# signal_processor_of_UAV.net
KiCad netlist of a schematic drawn in Altium Designer
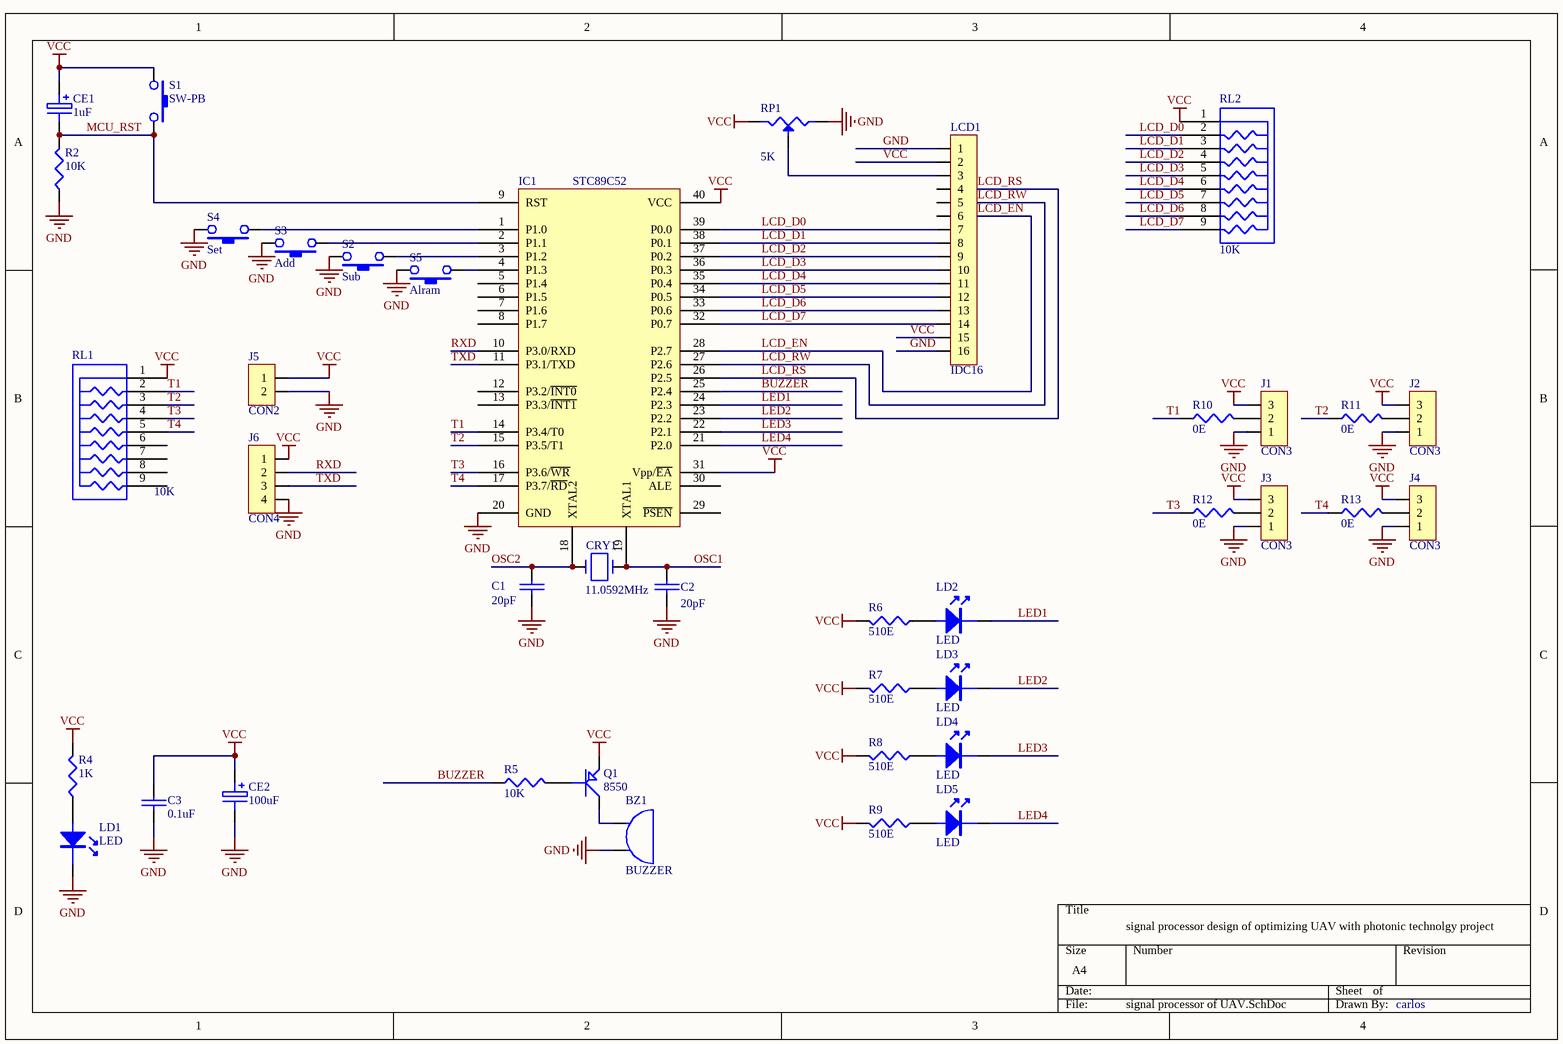
[diagram p0: signal processor of UAV.SchDoc]

(export (version "E")
  (design (tool "Eeschema 10.0.6"))
  (components
    (comp (ref "BZ1") (value "BUZZER") (footprint "BUZZER1") (libsource (lib "Sch1") (part "BUZZER")))
    (comp (ref "C1")
      (value "20pF")
      (footprint "RAD0.1")
      (description "Capacitor")
      (libsource (lib "*") (part "CAP"))
    )
    (comp (ref "C2")
      (value "20pF")
      (footprint "RAD0.1")
      (description "Capacitor")
      (libsource (lib "*") (part "CAP"))
    )
    (comp (ref "C3") (value "0.1uF") (footprint "RAD0.1") (libsource (lib "Sch1") (part "CAP")))
    (comp (ref "CE1") (value "1uF") (footprint "RB.1/.1L") (libsource (lib "Sch1") (part "ELECTRO1")))
    (comp (ref "CE2") (value "100uF") (footprint "RB.1/.2") (libsource (lib "Sch1") (part "ELECTRO1")))
    (comp (ref "CRY1") (value "11.0592MHz") (footprint "XTAL1") (libsource (lib "*") (part "CRYSTAL")))
    (comp (ref "IC1") (value "STC89C52") (footprint "DIP40") (libsource (lib "Sch") (part "AT89C51")))
    (comp (ref "J1") (value "CON3") (footprint "HJ3P2.54") (libsource (lib "Sch1") (part "CON3")))
    (comp (ref "J2") (value "CON3") (footprint "HJ3P2.54") (libsource (lib "Sch1") (part "CON3")))
    (comp (ref "J3") (value "CON3") (footprint "HJ3P2.54") (libsource (lib "Sch1") (part "CON3")))
    (comp (ref "J4") (value "CON3") (footprint "HJ3P2.54") (libsource (lib "Sch1") (part "CON3")))
    (comp (ref "J5") (value "CON2") (footprint "HJ2P2.54") (libsource (lib "Sch1") (part "CON2")))
    (comp (ref "J6") (value "CON4") (footprint "HJ4P2.54") (libsource (lib "Sch1") (part "CON4")))
    (comp (ref "LCD1") (value "IDC16") (footprint "LCD1602A") (libsource (lib "Sch1") (part "CON16")))
    (comp (ref "LD1") (value "LED") (footprint "LEDF3") (libsource (lib "Sch1") (part "LED")))
    (comp (ref "LD2") (value "LED") (footprint "LEDF3") (libsource (lib "Sch1") (part "LED")))
    (comp (ref "LD3") (value "LED") (footprint "LEDF3") (libsource (lib "Sch1") (part "LED")))
    (comp (ref "LD4") (value "LED") (footprint "LEDF3") (libsource (lib "Sch1") (part "LED")))
    (comp (ref "LD5") (value "LED") (footprint "LEDF3") (libsource (lib "Sch1") (part "LED")))
    (comp (ref "Q1") (value "8550") (footprint "TR-EBC") (libsource (lib "Sch1") (part "PNP1")))
    (comp (ref "R2") (value "10K") (footprint "AXIAL0.3") (libsource (lib "Sch1") (part "RES1")))
    (comp (ref "R4") (value "1K") (footprint "AXIAL0.3") (libsource (lib "Sch1") (part "RES1")))
    (comp (ref "R5") (value "10K") (footprint "AXIAL0.3") (libsource (lib "Sch1") (part "RES1")))
    (comp (ref "R6") (value "510E") (footprint "AXIAL0.3") (libsource (lib "Sch1") (part "RES1")))
    (comp (ref "R7") (value "510E") (footprint "AXIAL0.3") (libsource (lib "Sch1") (part "RES1")))
    (comp (ref "R8") (value "510E") (footprint "AXIAL0.3") (libsource (lib "Sch1") (part "RES1")))
    (comp (ref "R9") (value "510E") (footprint "AXIAL0.3") (libsource (lib "Sch1") (part "RES1")))
    (comp (ref "R10") (value "0E") (footprint "AXIAL0.3") (libsource (lib "Sch1") (part "RES1")))
    (comp (ref "R11") (value "0E") (footprint "AXIAL0.3") (libsource (lib "Sch1") (part "RES1")))
    (comp (ref "R12") (value "0E") (footprint "AXIAL0.3") (libsource (lib "Sch1") (part "RES1")))
    (comp (ref "R13") (value "0E") (footprint "AXIAL0.3") (libsource (lib "Sch1") (part "RES1")))
    (comp (ref "RL1") (value "10K") (footprint "RES9P") (libsource (lib "Sch1") (part "RESL1")))
    (comp (ref "RL2") (value "10K") (footprint "RES9P") (libsource (lib "Sch1") (part "RESL1")))
    (comp (ref "RP1") (value "5K") (footprint "WR1") (libsource (lib "Sch1") (part "POT1")))
    (comp (ref "S1") (value "SW-PB") (footprint "SW-PB4DS") (libsource (lib "Sch1") (part "SW-PB")))
    (comp (ref "S2") (value "Sub") (footprint "SW-PB4DS") (libsource (lib "Sch1") (part "SW-PB")))
    (comp (ref "S3") (value "Add") (footprint "SW-PB4DS") (libsource (lib "Sch1") (part "SW-PB")))
    (comp (ref "S4") (value "Set") (footprint "SW-PB4DS") (libsource (lib "Sch1") (part "SW-PB")))
    (comp (ref "S5") (value "Alram") (footprint "SW-PB4DS") (libsource (lib "Sch1") (part "SW-PB")))
  )
  (nets
    (net (code "1") (name "/BUZZER") (class "Default")
      (node (ref "IC1") (pin "25") (pinfunction "P2.4_25") (pintype "passive"))
      (node (ref "R5") (pin "1") (pintype "passive"))
    )
    (net (code "2") (name "/LCD_D0") (class "Default")
      (node (ref "IC1") (pin "39") (pinfunction "P0.0_39") (pintype "passive"))
      (node (ref "LCD1") (pin "7") (pinfunction "7_7") (pintype "passive"))
      (node (ref "RL2") (pin "2") (pinfunction "2_2") (pintype "passive"))
    )
    (net (code "3") (name "/LCD_D1") (class "Default")
      (node (ref "IC1") (pin "38") (pinfunction "P0.1_38") (pintype "passive"))
      (node (ref "LCD1") (pin "8") (pinfunction "8_8") (pintype "passive"))
      (node (ref "RL2") (pin "3") (pinfunction "3_3") (pintype "passive"))
    )
    (net (code "4") (name "/LCD_D2") (class "Default")
      (node (ref "IC1") (pin "37") (pinfunction "P0.2_37") (pintype "passive"))
      (node (ref "LCD1") (pin "9") (pinfunction "9_9") (pintype "passive"))
      (node (ref "RL2") (pin "4") (pinfunction "4_4") (pintype "passive"))
    )
    (net (code "5") (name "/LCD_D3") (class "Default")
      (node (ref "IC1") (pin "36") (pinfunction "P0.3_36") (pintype "passive"))
      (node (ref "LCD1") (pin "10") (pinfunction "10_10") (pintype "passive"))
      (node (ref "RL2") (pin "5") (pinfunction "5_5") (pintype "passive"))
    )
    (net (code "6") (name "/LCD_D4") (class "Default")
      (node (ref "IC1") (pin "35") (pinfunction "P0.4_35") (pintype "passive"))
      (node (ref "LCD1") (pin "11") (pinfunction "11_11") (pintype "passive"))
      (node (ref "RL2") (pin "6") (pinfunction "6_6") (pintype "passive"))
    )
    (net (code "7") (name "/LCD_D5") (class "Default")
      (node (ref "IC1") (pin "34") (pinfunction "P0.5_34") (pintype "passive"))
      (node (ref "LCD1") (pin "12") (pinfunction "12_12") (pintype "passive"))
      (node (ref "RL2") (pin "7") (pinfunction "7_7") (pintype "passive"))
    )
    (net (code "8") (name "/LCD_D6") (class "Default")
      (node (ref "IC1") (pin "33") (pinfunction "P0.6_33") (pintype "passive"))
      (node (ref "LCD1") (pin "13") (pinfunction "13_13") (pintype "passive"))
      (node (ref "RL2") (pin "8") (pinfunction "8_8") (pintype "passive"))
    )
    (net (code "9") (name "/LCD_D7") (class "Default")
      (node (ref "IC1") (pin "32") (pinfunction "P0.7_32") (pintype "passive"))
      (node (ref "LCD1") (pin "14") (pinfunction "14_14") (pintype "passive"))
      (node (ref "RL2") (pin "9") (pinfunction "9_9") (pintype "passive"))
    )
    (net (code "10") (name "/LCD_EN") (class "Default")
      (node (ref "IC1") (pin "28") (pinfunction "P2.7_28") (pintype "passive"))
    )
    (net (code "11") (name "/LCD_RS") (class "Default")
      (node (ref "IC1") (pin "26") (pinfunction "P2.5_26") (pintype "passive"))
    )
    (net (code "12") (name "/LCD_RW") (class "Default")
      (node (ref "IC1") (pin "27") (pinfunction "P2.6_27") (pintype "passive"))
    )
    (net (code "13") (name "/LED1") (class "Default")
      (node (ref "IC1") (pin "24") (pinfunction "P2.3_24") (pintype "passive"))
      (node (ref "LD2") (pin "K") (pintype "passive"))
    )
    (net (code "14") (name "/LED2") (class "Default")
      (node (ref "IC1") (pin "23") (pinfunction "P2.2_23") (pintype "passive"))
      (node (ref "LD3") (pin "K") (pintype "passive"))
    )
    (net (code "15") (name "/LED3") (class "Default")
      (node (ref "IC1") (pin "22") (pinfunction "P2.1_22") (pintype "passive"))
      (node (ref "LD4") (pin "K") (pintype "passive"))
    )
    (net (code "16") (name "/LED4") (class "Default")
      (node (ref "IC1") (pin "21") (pinfunction "P2.0_21") (pintype "passive"))
      (node (ref "LD5") (pin "K") (pintype "passive"))
    )
    (net (code "17") (name "/MCU_RST") (class "Default")
      (node (ref "CE1") (pin "2") (pintype "passive"))
      (node (ref "IC1") (pin "9") (pinfunction "RST_9") (pintype "passive"))
      (node (ref "R2") (pin "2") (pintype "passive"))
      (node (ref "S1") (pin "2") (pintype "passive"))
    )
    (net (code "18") (name "/OSC1") (class "Default")
      (node (ref "C2") (pin "1") (pinfunction "1_1") (pintype "passive"))
      (node (ref "CRY1") (pin "2") (pinfunction "2_2") (pintype "passive"))
      (node (ref "IC1") (pin "19") (pinfunction "XTAL1_19") (pintype "passive"))
    )
    (net (code "19") (name "/OSC2") (class "Default")
      (node (ref "C1") (pin "1") (pinfunction "1_1") (pintype "passive"))
      (node (ref "CRY1") (pin "1") (pinfunction "1_1") (pintype "passive"))
      (node (ref "IC1") (pin "18") (pinfunction "XTAL2_18") (pintype "passive"))
    )
    (net (code "20") (name "/RXD") (class "Default")
      (node (ref "IC1") (pin "10") (pinfunction "P3.0/RXD_10") (pintype "passive"))
      (node (ref "J6") (pin "2") (pinfunction "2_2") (pintype "passive"))
    )
    (net (code "21") (name "/T1") (class "Default")
      (node (ref "IC1") (pin "14") (pinfunction "P3.4/T0_14") (pintype "passive"))
      (node (ref "R10") (pin "1") (pintype "passive"))
      (node (ref "RL1") (pin "2") (pinfunction "2_2") (pintype "passive"))
    )
    (net (code "22") (name "/T2") (class "Default")
      (node (ref "IC1") (pin "15") (pinfunction "P3.5/T1_15") (pintype "passive"))
      (node (ref "R11") (pin "1") (pintype "passive"))
      (node (ref "RL1") (pin "3") (pinfunction "3_3") (pintype "passive"))
    )
    (net (code "23") (name "/T3") (class "Default")
      (node (ref "IC1") (pin "16") (pinfunction "P3.6/~{WR}_16") (pintype "passive"))
      (node (ref "R12") (pin "1") (pintype "passive"))
      (node (ref "RL1") (pin "4") (pinfunction "4_4") (pintype "passive"))
    )
    (net (code "24") (name "/T4") (class "Default")
      (node (ref "IC1") (pin "17") (pinfunction "P3.7/~{RD}_17") (pintype "passive"))
      (node (ref "R13") (pin "1") (pintype "passive"))
      (node (ref "RL1") (pin "5") (pinfunction "5_5") (pintype "passive"))
    )
    (net (code "25") (name "/TXD") (class "Default")
      (node (ref "IC1") (pin "11") (pinfunction "P3.1/TXD_11") (pintype "passive"))
      (node (ref "J6") (pin "3") (pinfunction "3_3") (pintype "passive"))
    )
    (net (code "26") (name "GND") (class "Default")
      (node (ref "BZ1") (pin "2") (pintype "passive"))
      (node (ref "C1") (pin "2") (pinfunction "2_2") (pintype "passive"))
      (node (ref "C2") (pin "2") (pinfunction "2_2") (pintype "passive"))
      (node (ref "C3") (pin "2") (pintype "passive"))
      (node (ref "CE2") (pin "2") (pintype "passive"))
      (node (ref "IC1") (pin "20") (pinfunction "GND_20") (pintype "passive"))
      (node (ref "J1") (pin "1") (pinfunction "1_1") (pintype "passive"))
      (node (ref "J2") (pin "1") (pinfunction "1_1") (pintype "passive"))
      (node (ref "J3") (pin "1") (pinfunction "1_1") (pintype "passive"))
      (node (ref "J4") (pin "1") (pinfunction "1_1") (pintype "passive"))
      (node (ref "J5") (pin "2") (pinfunction "2_2") (pintype "passive"))
      (node (ref "J6") (pin "4") (pinfunction "4_4") (pintype "passive"))
      (node (ref "LCD1") (pin "1") (pinfunction "1_1") (pintype "passive"))
      (node (ref "LCD1") (pin "16") (pinfunction "16_16") (pintype "passive"))
      (node (ref "LD1") (pin "K") (pintype "passive"))
      (node (ref "R2") (pin "1") (pintype "passive"))
      (node (ref "RP1") (pin "2") (pintype "passive"))
      (node (ref "S2") (pin "1") (pintype "passive"))
      (node (ref "S3") (pin "1") (pintype "passive"))
      (node (ref "S4") (pin "1") (pintype "passive"))
      (node (ref "S5") (pin "1") (pintype "passive"))
    )
    (net (code "27") (name "Net-(BZ1-Pad1)") (class "Default")
      (node (ref "BZ1") (pin "1") (pintype "passive"))
      (node (ref "Q1") (pin "COLL") (pinfunction "COLL_COLL") (pintype "passive"))
    )
    (net (code "28") (name "Net-(IC1-P1.0)") (class "Default")
      (node (ref "IC1") (pin "1") (pinfunction "P1.0_1") (pintype "passive"))
      (node (ref "S4") (pin "2") (pintype "passive"))
    )
    (net (code "29") (name "Net-(IC1-P1.1)") (class "Default")
      (node (ref "IC1") (pin "2") (pinfunction "P1.1_2") (pintype "passive"))
      (node (ref "S3") (pin "2") (pintype "passive"))
    )
    (net (code "30") (name "Net-(IC1-P1.2)") (class "Default")
      (node (ref "IC1") (pin "3") (pinfunction "P1.2_3") (pintype "passive"))
      (node (ref "S2") (pin "2") (pintype "passive"))
    )
    (net (code "31") (name "Net-(IC1-P1.3)") (class "Default")
      (node (ref "IC1") (pin "4") (pinfunction "P1.3_4") (pintype "passive"))
      (node (ref "S5") (pin "2") (pintype "passive"))
    )
    (net (code "32") (name "Net-(J1-Pad2)") (class "Default")
      (node (ref "J1") (pin "2") (pinfunction "2_2") (pintype "passive"))
      (node (ref "R10") (pin "2") (pintype "passive"))
    )
    (net (code "33") (name "Net-(J2-Pad2)") (class "Default")
      (node (ref "J2") (pin "2") (pinfunction "2_2") (pintype "passive"))
      (node (ref "R11") (pin "2") (pintype "passive"))
    )
    (net (code "34") (name "Net-(J3-Pad2)") (class "Default")
      (node (ref "J3") (pin "2") (pinfunction "2_2") (pintype "passive"))
      (node (ref "R12") (pin "2") (pintype "passive"))
    )
    (net (code "35") (name "Net-(J4-Pad2)") (class "Default")
      (node (ref "J4") (pin "2") (pinfunction "2_2") (pintype "passive"))
      (node (ref "R13") (pin "2") (pintype "passive"))
    )
    (net (code "36") (name "Net-(LCD1-Pad3)") (class "Default")
      (node (ref "LCD1") (pin "3") (pinfunction "3_3") (pintype "passive"))
      (node (ref "RP1") (pin "W") (pintype "passive"))
    )
    (net (code "37") (name "Net-(LD1-PadA)") (class "Default")
      (node (ref "LD1") (pin "A") (pintype "passive"))
      (node (ref "R4") (pin "1") (pintype "passive"))
    )
    (net (code "38") (name "Net-(LD2-PadA)") (class "Default")
      (node (ref "LD2") (pin "A") (pintype "passive"))
      (node (ref "R6") (pin "1") (pintype "passive"))
    )
    (net (code "39") (name "Net-(LD3-PadA)") (class "Default")
      (node (ref "LD3") (pin "A") (pintype "passive"))
      (node (ref "R7") (pin "1") (pintype "passive"))
    )
    (net (code "40") (name "Net-(LD4-PadA)") (class "Default")
      (node (ref "LD4") (pin "A") (pintype "passive"))
      (node (ref "R8") (pin "1") (pintype "passive"))
    )
    (net (code "41") (name "Net-(LD5-PadA)") (class "Default")
      (node (ref "LD5") (pin "A") (pintype "passive"))
      (node (ref "R9") (pin "1") (pintype "passive"))
    )
    (net (code "42") (name "Net-(Q1-PadBASE)") (class "Default")
      (node (ref "Q1") (pin "BASE") (pinfunction "BASE_BASE") (pintype "passive"))
      (node (ref "R5") (pin "2") (pintype "passive"))
    )
    (net (code "43") (name "VCC") (class "Default")
      (node (ref "C3") (pin "1") (pintype "passive"))
      (node (ref "CE1") (pin "1") (pintype "passive"))
      (node (ref "CE2") (pin "1") (pintype "passive"))
      (node (ref "IC1") (pin "31") (pinfunction "Vpp/~{EA}_31") (pintype "passive"))
      (node (ref "IC1") (pin "40") (pinfunction "VCC_40") (pintype "passive"))
      (node (ref "J1") (pin "3") (pinfunction "3_3") (pintype "passive"))
      (node (ref "J2") (pin "3") (pinfunction "3_3") (pintype "passive"))
      (node (ref "J3") (pin "3") (pinfunction "3_3") (pintype "passive"))
      (node (ref "J4") (pin "3") (pinfunction "3_3") (pintype "passive"))
      (node (ref "J5") (pin "1") (pinfunction "1_1") (pintype "passive"))
      (node (ref "J6") (pin "1") (pinfunction "1_1") (pintype "passive"))
      (node (ref "LCD1") (pin "15") (pinfunction "15_15") (pintype "passive"))
      (node (ref "LCD1") (pin "2") (pinfunction "2_2") (pintype "passive"))
      (node (ref "Q1") (pin "EMIT") (pinfunction "EMIT_EMIT") (pintype "passive"))
      (node (ref "R4") (pin "2") (pintype "passive"))
      (node (ref "R6") (pin "2") (pintype "passive"))
      (node (ref "R7") (pin "2") (pintype "passive"))
      (node (ref "R8") (pin "2") (pintype "passive"))
      (node (ref "R9") (pin "2") (pintype "passive"))
      (node (ref "RL1") (pin "1") (pinfunction "1_1") (pintype "passive"))
      (node (ref "RL2") (pin "1") (pinfunction "1_1") (pintype "passive"))
      (node (ref "RP1") (pin "1") (pintype "passive"))
      (node (ref "S1") (pin "1") (pintype "passive"))
    )
    (net (code "44") (name "unconnected-(IC1-ALE-Pad30)") (class "Default")
      (node (ref "IC1") (pin "30") (pinfunction "ALE_30") (pintype "passive"))
    )
    (net (code "45") (name "unconnected-(IC1-P1.4-Pad5)") (class "Default")
      (node (ref "IC1") (pin "5") (pinfunction "P1.4_5") (pintype "passive"))
    )
    (net (code "46") (name "unconnected-(IC1-P1.5-Pad6)") (class "Default")
      (node (ref "IC1") (pin "6") (pinfunction "P1.5_6") (pintype "passive"))
    )
    (net (code "47") (name "unconnected-(IC1-P1.6-Pad7)") (class "Default")
      (node (ref "IC1") (pin "7") (pinfunction "P1.6_7") (pintype "passive"))
    )
    (net (code "48") (name "unconnected-(IC1-P1.7-Pad8)") (class "Default")
      (node (ref "IC1") (pin "8") (pinfunction "P1.7_8") (pintype "passive"))
    )
    (net (code "49") (name "unconnected-(IC1-P3.2{slash}~{INT0}-Pad12)") (class "Default")
      (node (ref "IC1") (pin "12") (pinfunction "P3.2/~{INT0}_12") (pintype "passive"))
    )
    (net (code "50") (name "unconnected-(IC1-P3.3{slash}~{INT1}-Pad13)") (class "Default")
      (node (ref "IC1") (pin "13") (pinfunction "P3.3/~{INT1}_13") (pintype "passive"))
    )
    (net (code "51") (name "unconnected-(IC1-~{PSEN}-Pad29)") (class "Default")
      (node (ref "IC1") (pin "29") (pinfunction "~{PSEN}_29") (pintype "passive"))
    )
    (net (code "52") (name "unconnected-(LCD1-Pad4)") (class "Default")
      (node (ref "LCD1") (pin "4") (pinfunction "4_4") (pintype "passive"))
    )
    (net (code "53") (name "unconnected-(LCD1-Pad5)") (class "Default")
      (node (ref "LCD1") (pin "5") (pinfunction "5_5") (pintype "passive"))
    )
    (net (code "54") (name "unconnected-(LCD1-Pad6)") (class "Default")
      (node (ref "LCD1") (pin "6") (pinfunction "6_6") (pintype "passive"))
    )
    (net (code "55") (name "unconnected-(RL1-Pad6)") (class "Default")
      (node (ref "RL1") (pin "6") (pinfunction "6_6") (pintype "passive"))
    )
    (net (code "56") (name "unconnected-(RL1-Pad7)") (class "Default")
      (node (ref "RL1") (pin "7") (pinfunction "7_7") (pintype "passive"))
    )
    (net (code "57") (name "unconnected-(RL1-Pad8)") (class "Default")
      (node (ref "RL1") (pin "8") (pinfunction "8_8") (pintype "passive"))
    )
    (net (code "58") (name "unconnected-(RL1-Pad9)") (class "Default")
      (node (ref "RL1") (pin "9") (pinfunction "9_9") (pintype "passive"))
    )
  )
)
